# Pow_Dist_24_12_5v.net
KiCad netlist of a schematic drawn in Altium Designer
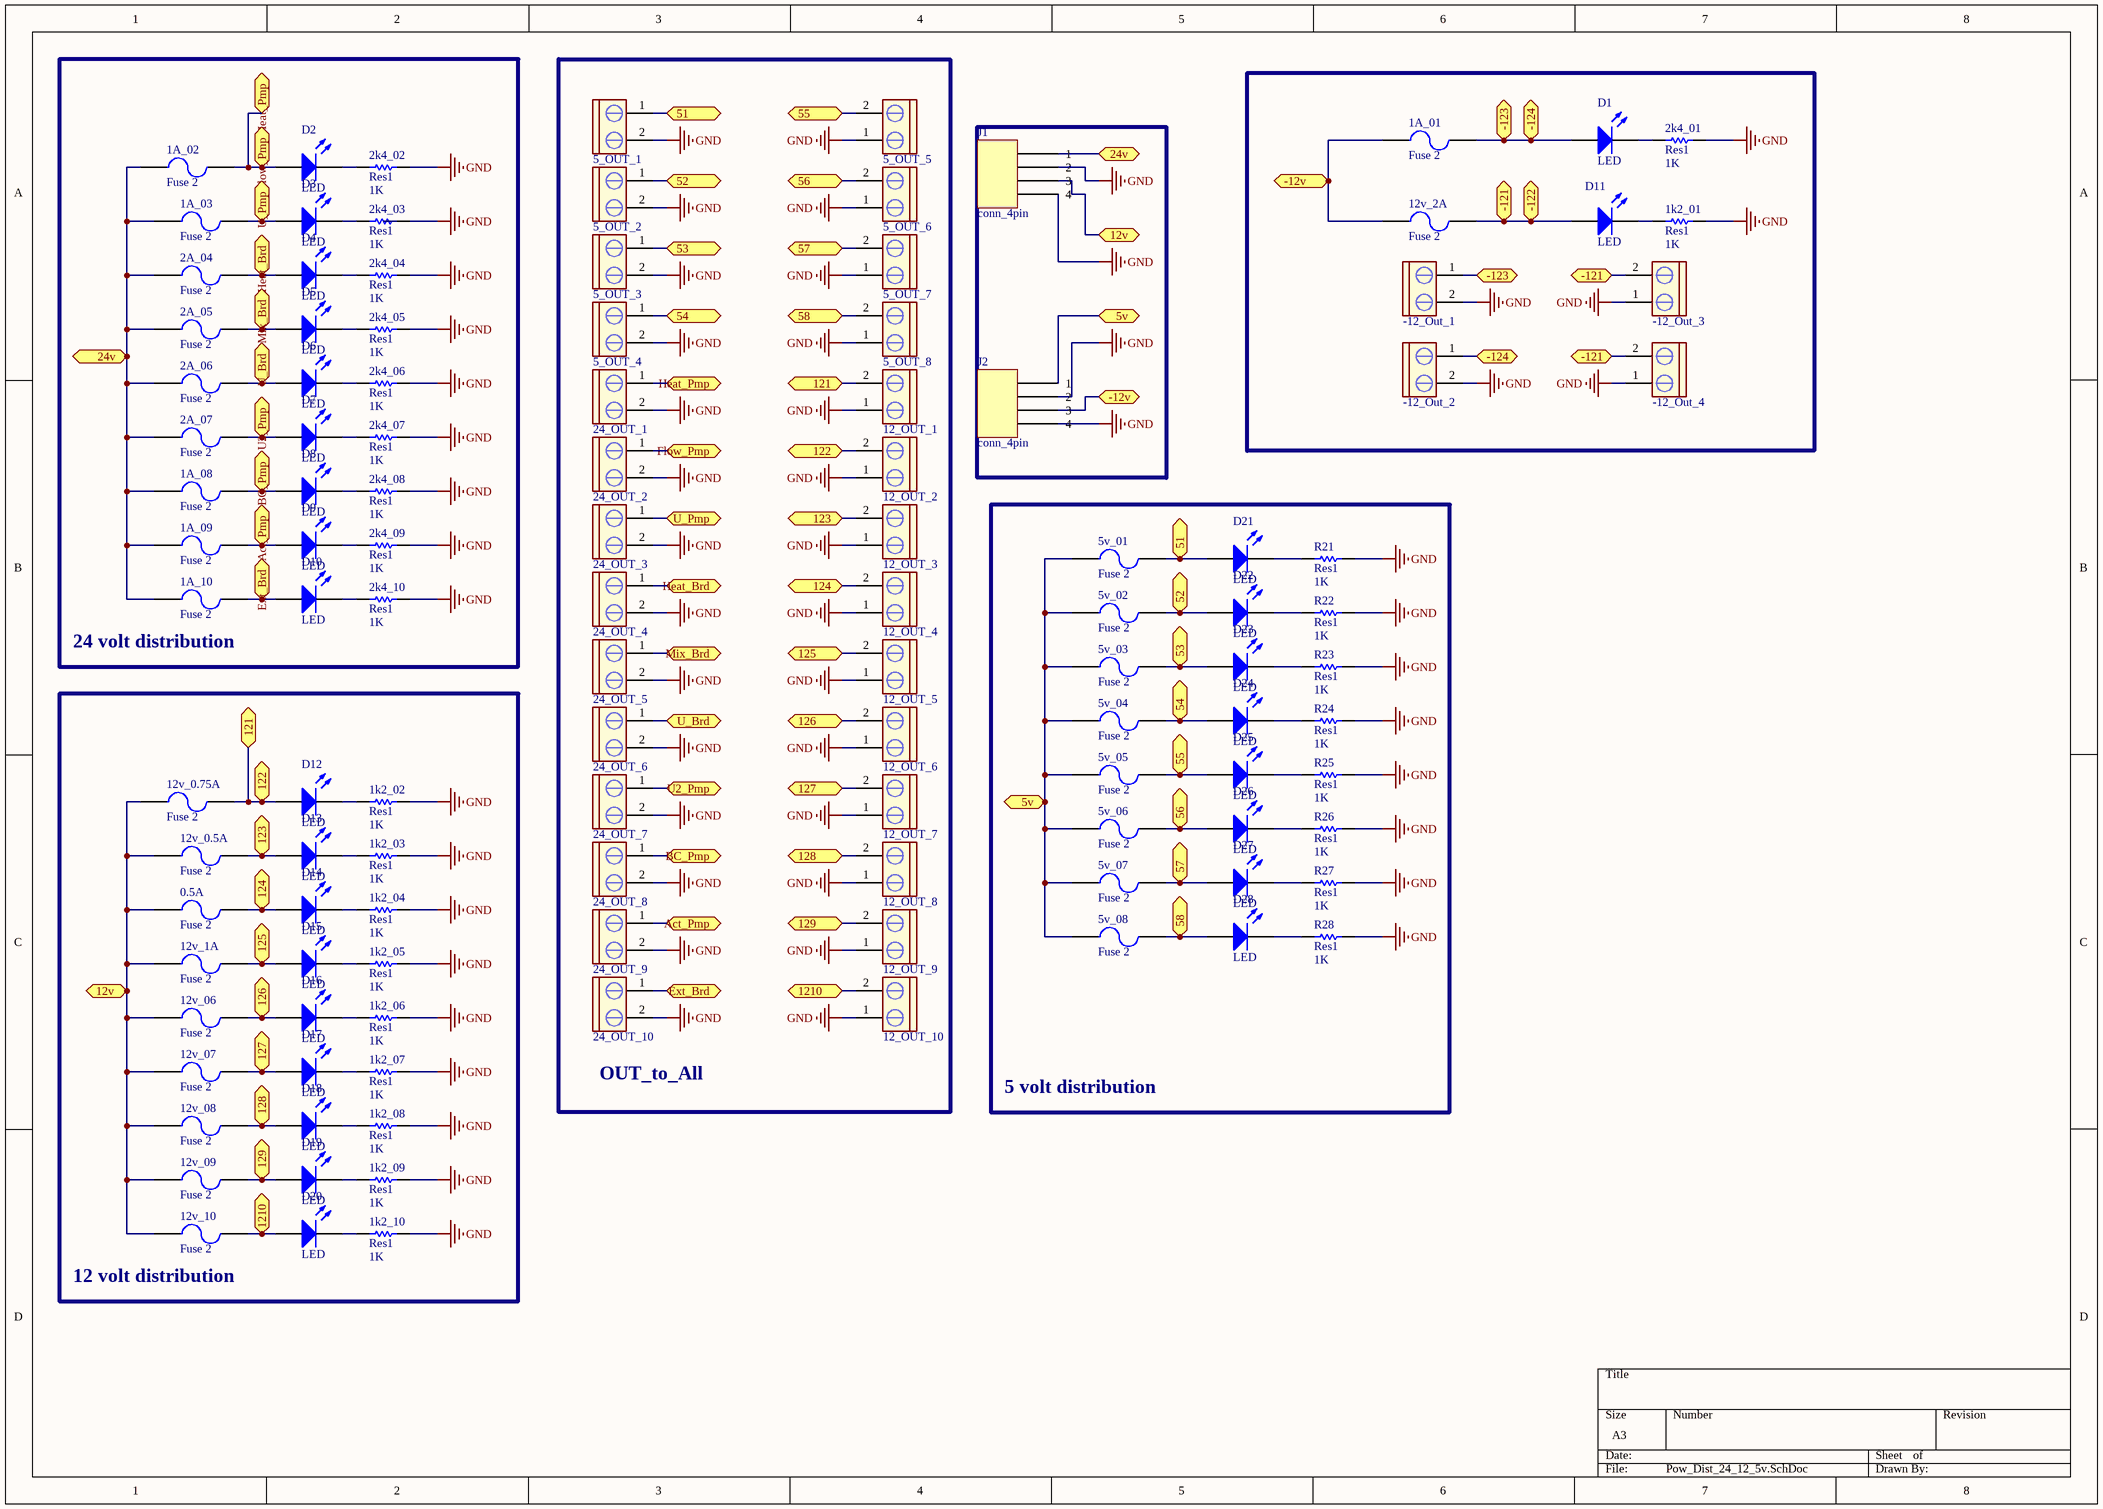
[diagram p0: Pow_Dist_24_12_5v.SchDoc]

(export (version "E")
  (design (tool "Eeschema 10.0.6"))
  (components
    (comp (ref "-12_Out_1")
      (value "CON2 pin blue")
      (footprint "My_CN2")
      (description "Connector blue screw")
      (libsource (lib "Mylib") (part "CON2 pin blue"))
    )
    (comp (ref "-12_Out_2")
      (value "CON2 pin blue")
      (footprint "My_CN2")
      (description "Connector blue screw")
      (libsource (lib "Mylib") (part "CON2 pin blue"))
    )
    (comp (ref "-12_Out_3")
      (value "CON2 pin blue")
      (footprint "My_CN2")
      (description "Connector blue screw")
      (libsource (lib "") (part "CON2 pin blue_1"))
    )
    (comp (ref "-12_Out_4")
      (value "CON2 pin blue")
      (footprint "My_CN2")
      (description "Connector blue screw")
      (libsource (lib "") (part "CON2 pin blue_1"))
    )
    (comp (ref "0.5A")
      (value "Fuse 2")
      (footprint "FUSE:PCBComponent_1")
      (description "Fuse")
      (fields (field (name "PUBLISHER") "Altium Limited"))
      (libsource (lib "Miscellaneous Devices") (part "Fuse 2"))
    )
    (comp (ref "1A_01")
      (value "Fuse 2")
      (footprint "FUSE:PCBComponent_1")
      (description "Fuse")
      (fields (field (name "PUBLISHER") "Altium Limited"))
      (libsource (lib "Miscellaneous Devices") (part "Fuse 2"))
    )
    (comp (ref "1A_02")
      (value "Fuse 2")
      (footprint "FUSE:PCBComponent_1")
      (description "Fuse")
      (fields (field (name "PUBLISHER") "Altium Limited"))
      (libsource (lib "Miscellaneous Devices") (part "Fuse 2"))
    )
    (comp (ref "1A_03")
      (value "Fuse 2")
      (footprint "FUSE:PCBComponent_1")
      (description "Fuse")
      (fields (field (name "PUBLISHER") "Altium Limited"))
      (libsource (lib "Miscellaneous Devices") (part "Fuse 2"))
    )
    (comp (ref "1A_08")
      (value "Fuse 2")
      (footprint "FUSE:PCBComponent_1")
      (description "Fuse")
      (fields (field (name "PUBLISHER") "Altium Limited"))
      (libsource (lib "Miscellaneous Devices") (part "Fuse 2"))
    )
    (comp (ref "1A_09")
      (value "Fuse 2")
      (footprint "FUSE:PCBComponent_1")
      (description "Fuse")
      (fields (field (name "PUBLISHER") "Altium Limited"))
      (libsource (lib "Miscellaneous Devices") (part "Fuse 2"))
    )
    (comp (ref "1A_10")
      (value "Fuse 2")
      (footprint "FUSE:PCBComponent_1")
      (description "Fuse")
      (fields (field (name "PUBLISHER") "Altium Limited"))
      (libsource (lib "Miscellaneous Devices") (part "Fuse 2"))
    )
    (comp (ref "1k2_01")
      (value "Res1")
      (footprint "AXIAL-0.3")
      (description "Resistor")
      (fields (field (name "ALTIUM_VALUE") "1K") (field (name "PUBLISHER") "Altium Limited"))
      (libsource (lib "Miscellaneous Devices") (part "Res1"))
    )
    (comp (ref "1k2_02")
      (value "Res1")
      (footprint "AXIAL-0.3")
      (description "Resistor")
      (fields (field (name "ALTIUM_VALUE") "1K") (field (name "PUBLISHER") "Altium Limited"))
      (libsource (lib "Miscellaneous Devices") (part "Res1"))
    )
    (comp (ref "1k2_03")
      (value "Res1")
      (footprint "AXIAL-0.3")
      (description "Resistor")
      (fields (field (name "ALTIUM_VALUE") "1K") (field (name "PUBLISHER") "Altium Limited"))
      (libsource (lib "Miscellaneous Devices") (part "Res1"))
    )
    (comp (ref "1k2_04")
      (value "Res1")
      (footprint "AXIAL-0.3")
      (description "Resistor")
      (fields (field (name "ALTIUM_VALUE") "1K") (field (name "PUBLISHER") "Altium Limited"))
      (libsource (lib "Miscellaneous Devices") (part "Res1"))
    )
    (comp (ref "1k2_05")
      (value "Res1")
      (footprint "AXIAL-0.3")
      (description "Resistor")
      (fields (field (name "ALTIUM_VALUE") "1K") (field (name "PUBLISHER") "Altium Limited"))
      (libsource (lib "Miscellaneous Devices") (part "Res1"))
    )
    (comp (ref "1k2_06")
      (value "Res1")
      (footprint "AXIAL-0.3")
      (description "Resistor")
      (fields (field (name "ALTIUM_VALUE") "1K") (field (name "PUBLISHER") "Altium Limited"))
      (libsource (lib "Miscellaneous Devices") (part "Res1"))
    )
    (comp (ref "1k2_07")
      (value "Res1")
      (footprint "AXIAL-0.3")
      (description "Resistor")
      (fields (field (name "ALTIUM_VALUE") "1K") (field (name "PUBLISHER") "Altium Limited"))
      (libsource (lib "Miscellaneous Devices") (part "Res1"))
    )
    (comp (ref "1k2_08")
      (value "Res1")
      (footprint "AXIAL-0.3")
      (description "Resistor")
      (fields (field (name "ALTIUM_VALUE") "1K") (field (name "PUBLISHER") "Altium Limited"))
      (libsource (lib "Miscellaneous Devices") (part "Res1"))
    )
    (comp (ref "1k2_09")
      (value "Res1")
      (footprint "AXIAL-0.3")
      (description "Resistor")
      (fields (field (name "ALTIUM_VALUE") "1K") (field (name "PUBLISHER") "Altium Limited"))
      (libsource (lib "Miscellaneous Devices") (part "Res1"))
    )
    (comp (ref "1k2_10")
      (value "Res1")
      (footprint "AXIAL-0.3")
      (description "Resistor")
      (fields (field (name "ALTIUM_VALUE") "1K") (field (name "PUBLISHER") "Altium Limited"))
      (libsource (lib "Miscellaneous Devices") (part "Res1"))
    )
    (comp (ref "2A_04")
      (value "Fuse 2")
      (footprint "FUSE:PCBComponent_1")
      (description "Fuse")
      (fields (field (name "PUBLISHER") "Altium Limited"))
      (libsource (lib "Miscellaneous Devices") (part "Fuse 2"))
    )
    (comp (ref "2A_05")
      (value "Fuse 2")
      (footprint "FUSE:PCBComponent_1")
      (description "Fuse")
      (fields (field (name "PUBLISHER") "Altium Limited"))
      (libsource (lib "Miscellaneous Devices") (part "Fuse 2"))
    )
    (comp (ref "2A_06")
      (value "Fuse 2")
      (footprint "FUSE:PCBComponent_1")
      (description "Fuse")
      (fields (field (name "PUBLISHER") "Altium Limited"))
      (libsource (lib "Miscellaneous Devices") (part "Fuse 2"))
    )
    (comp (ref "2A_07")
      (value "Fuse 2")
      (footprint "FUSE:PCBComponent_1")
      (description "Fuse")
      (fields (field (name "PUBLISHER") "Altium Limited"))
      (libsource (lib "Miscellaneous Devices") (part "Fuse 2"))
    )
    (comp (ref "2k4_01")
      (value "Res1")
      (footprint "AXIAL-0.3")
      (description "Resistor")
      (fields (field (name "ALTIUM_VALUE") "1K") (field (name "PUBLISHER") "Altium Limited"))
      (libsource (lib "Miscellaneous Devices") (part "Res1"))
    )
    (comp (ref "2k4_02")
      (value "Res1")
      (footprint "AXIAL-0.3")
      (description "Resistor")
      (fields (field (name "ALTIUM_VALUE") "1K") (field (name "PUBLISHER") "Altium Limited"))
      (libsource (lib "Miscellaneous Devices") (part "Res1"))
    )
    (comp (ref "2k4_03")
      (value "Res1")
      (footprint "AXIAL-0.3")
      (description "Resistor")
      (fields (field (name "ALTIUM_VALUE") "1K") (field (name "PUBLISHER") "Altium Limited"))
      (libsource (lib "Miscellaneous Devices") (part "Res1"))
    )
    (comp (ref "2k4_04")
      (value "Res1")
      (footprint "AXIAL-0.3")
      (description "Resistor")
      (fields (field (name "ALTIUM_VALUE") "1K") (field (name "PUBLISHER") "Altium Limited"))
      (libsource (lib "Miscellaneous Devices") (part "Res1"))
    )
    (comp (ref "2k4_05")
      (value "Res1")
      (footprint "AXIAL-0.3")
      (description "Resistor")
      (fields (field (name "ALTIUM_VALUE") "1K") (field (name "PUBLISHER") "Altium Limited"))
      (libsource (lib "Miscellaneous Devices") (part "Res1"))
    )
    (comp (ref "2k4_06")
      (value "Res1")
      (footprint "AXIAL-0.3")
      (description "Resistor")
      (fields (field (name "ALTIUM_VALUE") "1K") (field (name "PUBLISHER") "Altium Limited"))
      (libsource (lib "Miscellaneous Devices") (part "Res1"))
    )
    (comp (ref "2k4_07")
      (value "Res1")
      (footprint "AXIAL-0.3")
      (description "Resistor")
      (fields (field (name "ALTIUM_VALUE") "1K") (field (name "PUBLISHER") "Altium Limited"))
      (libsource (lib "Miscellaneous Devices") (part "Res1"))
    )
    (comp (ref "2k4_08")
      (value "Res1")
      (footprint "AXIAL-0.3")
      (description "Resistor")
      (fields (field (name "ALTIUM_VALUE") "1K") (field (name "PUBLISHER") "Altium Limited"))
      (libsource (lib "Miscellaneous Devices") (part "Res1"))
    )
    (comp (ref "2k4_09")
      (value "Res1")
      (footprint "AXIAL-0.3")
      (description "Resistor")
      (fields (field (name "ALTIUM_VALUE") "1K") (field (name "PUBLISHER") "Altium Limited"))
      (libsource (lib "Miscellaneous Devices") (part "Res1"))
    )
    (comp (ref "2k4_10")
      (value "Res1")
      (footprint "AXIAL-0.3")
      (description "Resistor")
      (fields (field (name "ALTIUM_VALUE") "1K") (field (name "PUBLISHER") "Altium Limited"))
      (libsource (lib "Miscellaneous Devices") (part "Res1"))
    )
    (comp (ref "5v_01")
      (value "Fuse 2")
      (footprint "FUSE:PCBComponent_1")
      (description "Fuse")
      (fields (field (name "PUBLISHER") "Altium Limited"))
      (libsource (lib "Miscellaneous Devices") (part "Fuse 2"))
    )
    (comp (ref "5v_02")
      (value "Fuse 2")
      (footprint "FUSE:PCBComponent_1")
      (description "Fuse")
      (fields (field (name "PUBLISHER") "Altium Limited"))
      (libsource (lib "Miscellaneous Devices") (part "Fuse 2"))
    )
    (comp (ref "5v_03")
      (value "Fuse 2")
      (footprint "FUSE:PCBComponent_1")
      (description "Fuse")
      (fields (field (name "PUBLISHER") "Altium Limited"))
      (libsource (lib "Miscellaneous Devices") (part "Fuse 2"))
    )
    (comp (ref "5v_04")
      (value "Fuse 2")
      (footprint "FUSE:PCBComponent_1")
      (description "Fuse")
      (fields (field (name "PUBLISHER") "Altium Limited"))
      (libsource (lib "Miscellaneous Devices") (part "Fuse 2"))
    )
    (comp (ref "5v_05")
      (value "Fuse 2")
      (footprint "FUSE:PCBComponent_1")
      (description "Fuse")
      (fields (field (name "PUBLISHER") "Altium Limited"))
      (libsource (lib "Miscellaneous Devices") (part "Fuse 2"))
    )
    (comp (ref "5v_06")
      (value "Fuse 2")
      (footprint "FUSE:PCBComponent_1")
      (description "Fuse")
      (fields (field (name "PUBLISHER") "Altium Limited"))
      (libsource (lib "Miscellaneous Devices") (part "Fuse 2"))
    )
    (comp (ref "5v_07")
      (value "Fuse 2")
      (footprint "FUSE:PCBComponent_1")
      (description "Fuse")
      (fields (field (name "PUBLISHER") "Altium Limited"))
      (libsource (lib "Miscellaneous Devices") (part "Fuse 2"))
    )
    (comp (ref "5v_08")
      (value "Fuse 2")
      (footprint "FUSE:PCBComponent_1")
      (description "Fuse")
      (fields (field (name "PUBLISHER") "Altium Limited"))
      (libsource (lib "Miscellaneous Devices") (part "Fuse 2"))
    )
    (comp (ref "5_OUT_1")
      (value "CON2 pin blue")
      (footprint "My_CN2")
      (description "Connector blue screw")
      (libsource (lib "Mylib") (part "CON2 pin blue"))
    )
    (comp (ref "5_OUT_2")
      (value "CON2 pin blue")
      (footprint "My_CN2")
      (description "Connector blue screw")
      (libsource (lib "Mylib") (part "CON2 pin blue"))
    )
    (comp (ref "5_OUT_3")
      (value "CON2 pin blue")
      (footprint "My_CN2")
      (description "Connector blue screw")
      (libsource (lib "Mylib") (part "CON2 pin blue"))
    )
    (comp (ref "5_OUT_4")
      (value "CON2 pin blue")
      (footprint "My_CN2")
      (description "Connector blue screw")
      (libsource (lib "Mylib") (part "CON2 pin blue"))
    )
    (comp (ref "5_OUT_5")
      (value "CON2 pin blue")
      (footprint "My_CN2")
      (description "Connector blue screw")
      (libsource (lib "") (part "CON2 pin blue_1"))
    )
    (comp (ref "5_OUT_6")
      (value "CON2 pin blue")
      (footprint "My_CN2")
      (description "Connector blue screw")
      (libsource (lib "") (part "CON2 pin blue_1"))
    )
    (comp (ref "5_OUT_7")
      (value "CON2 pin blue")
      (footprint "My_CN2")
      (description "Connector blue screw")
      (libsource (lib "") (part "CON2 pin blue_1"))
    )
    (comp (ref "5_OUT_8")
      (value "CON2 pin blue")
      (footprint "My_CN2")
      (description "Connector blue screw")
      (libsource (lib "") (part "CON2 pin blue_1"))
    )
    (comp (ref "12v_0.5A")
      (value "Fuse 2")
      (footprint "FUSE:PCBComponent_1")
      (description "Fuse")
      (fields (field (name "PUBLISHER") "Altium Limited"))
      (libsource (lib "Miscellaneous Devices") (part "Fuse 2"))
    )
    (comp (ref "12v_0.75A")
      (value "Fuse 2")
      (footprint "FUSE:PCBComponent_1")
      (description "Fuse")
      (fields (field (name "PUBLISHER") "Altium Limited"))
      (libsource (lib "Miscellaneous Devices") (part "Fuse 2"))
    )
    (comp (ref "12v_1A")
      (value "Fuse 2")
      (footprint "FUSE:PCBComponent_1")
      (description "Fuse")
      (fields (field (name "PUBLISHER") "Altium Limited"))
      (libsource (lib "Miscellaneous Devices") (part "Fuse 2"))
    )
    (comp (ref "12v_2A")
      (value "Fuse 2")
      (footprint "FUSE:PCBComponent_1")
      (description "Fuse")
      (fields (field (name "PUBLISHER") "Altium Limited"))
      (libsource (lib "Miscellaneous Devices") (part "Fuse 2"))
    )
    (comp (ref "12v_06")
      (value "Fuse 2")
      (footprint "FUSE:PCBComponent_1")
      (description "Fuse")
      (fields (field (name "PUBLISHER") "Altium Limited"))
      (libsource (lib "Miscellaneous Devices") (part "Fuse 2"))
    )
    (comp (ref "12v_07")
      (value "Fuse 2")
      (footprint "FUSE:PCBComponent_1")
      (description "Fuse")
      (fields (field (name "PUBLISHER") "Altium Limited"))
      (libsource (lib "Miscellaneous Devices") (part "Fuse 2"))
    )
    (comp (ref "12v_08")
      (value "Fuse 2")
      (footprint "FUSE:PCBComponent_1")
      (description "Fuse")
      (fields (field (name "PUBLISHER") "Altium Limited"))
      (libsource (lib "Miscellaneous Devices") (part "Fuse 2"))
    )
    (comp (ref "12v_09")
      (value "Fuse 2")
      (footprint "FUSE:PCBComponent_1")
      (description "Fuse")
      (fields (field (name "PUBLISHER") "Altium Limited"))
      (libsource (lib "Miscellaneous Devices") (part "Fuse 2"))
    )
    (comp (ref "12v_10")
      (value "Fuse 2")
      (footprint "FUSE:PCBComponent_1")
      (description "Fuse")
      (fields (field (name "PUBLISHER") "Altium Limited"))
      (libsource (lib "Miscellaneous Devices") (part "Fuse 2"))
    )
    (comp (ref "12_OUT_1")
      (value "CON2 pin blue")
      (footprint "My_CN2")
      (description "Connector blue screw")
      (libsource (lib "") (part "CON2 pin blue_1"))
    )
    (comp (ref "12_OUT_2")
      (value "CON2 pin blue")
      (footprint "My_CN2")
      (description "Connector blue screw")
      (libsource (lib "") (part "CON2 pin blue_1"))
    )
    (comp (ref "12_OUT_3")
      (value "CON2 pin blue")
      (footprint "My_CN2")
      (description "Connector blue screw")
      (libsource (lib "") (part "CON2 pin blue_1"))
    )
    (comp (ref "12_OUT_4")
      (value "CON2 pin blue")
      (footprint "My_CN2")
      (description "Connector blue screw")
      (libsource (lib "") (part "CON2 pin blue_1"))
    )
    (comp (ref "12_OUT_5")
      (value "CON2 pin blue")
      (footprint "My_CN2")
      (description "Connector blue screw")
      (libsource (lib "") (part "CON2 pin blue_1"))
    )
    (comp (ref "12_OUT_6")
      (value "CON2 pin blue")
      (footprint "My_CN2")
      (description "Connector blue screw")
      (libsource (lib "") (part "CON2 pin blue_1"))
    )
    (comp (ref "12_OUT_7")
      (value "CON2 pin blue")
      (footprint "My_CN2")
      (description "Connector blue screw")
      (libsource (lib "") (part "CON2 pin blue_1"))
    )
    (comp (ref "12_OUT_8")
      (value "CON2 pin blue")
      (footprint "My_CN2")
      (description "Connector blue screw")
      (libsource (lib "") (part "CON2 pin blue_1"))
    )
    (comp (ref "12_OUT_9")
      (value "CON2 pin blue")
      (footprint "My_CN2")
      (description "Connector blue screw")
      (libsource (lib "") (part "CON2 pin blue_1"))
    )
    (comp (ref "12_OUT_10")
      (value "CON2 pin blue")
      (footprint "My_CN2")
      (description "Connector blue screw")
      (libsource (lib "") (part "CON2 pin blue_1"))
    )
    (comp (ref "24_OUT_1")
      (value "CON2 pin blue")
      (footprint "My_CN2")
      (description "Connector blue screw")
      (libsource (lib "Mylib") (part "CON2 pin blue"))
    )
    (comp (ref "24_OUT_2")
      (value "CON2 pin blue")
      (footprint "My_CN2")
      (description "Connector blue screw")
      (libsource (lib "Mylib") (part "CON2 pin blue"))
    )
    (comp (ref "24_OUT_3")
      (value "CON2 pin blue")
      (footprint "My_CN2")
      (description "Connector blue screw")
      (libsource (lib "Mylib") (part "CON2 pin blue"))
    )
    (comp (ref "24_OUT_4")
      (value "CON2 pin blue")
      (footprint "My_CN2")
      (description "Connector blue screw")
      (libsource (lib "Mylib") (part "CON2 pin blue"))
    )
    (comp (ref "24_OUT_5")
      (value "CON2 pin blue")
      (footprint "My_CN2")
      (description "Connector blue screw")
      (libsource (lib "Mylib") (part "CON2 pin blue"))
    )
    (comp (ref "24_OUT_6")
      (value "CON2 pin blue")
      (footprint "My_CN2")
      (description "Connector blue screw")
      (libsource (lib "Mylib") (part "CON2 pin blue"))
    )
    (comp (ref "24_OUT_7")
      (value "CON2 pin blue")
      (footprint "My_CN2")
      (description "Connector blue screw")
      (libsource (lib "Mylib") (part "CON2 pin blue"))
    )
    (comp (ref "24_OUT_8")
      (value "CON2 pin blue")
      (footprint "My_CN2")
      (description "Connector blue screw")
      (libsource (lib "Mylib") (part "CON2 pin blue"))
    )
    (comp (ref "24_OUT_9")
      (value "CON2 pin blue")
      (footprint "My_CN2")
      (description "Connector blue screw")
      (libsource (lib "Mylib") (part "CON2 pin blue"))
    )
    (comp (ref "24_OUT_10")
      (value "CON2 pin blue")
      (footprint "My_CN2")
      (description "Connector blue screw")
      (libsource (lib "Mylib") (part "CON2 pin blue"))
    )
    (comp (ref "D1")
      (value "LED")
      (footprint "My_LED3MM")
      (description "Typical INFRARED GaAs LED")
      (fields (field (name "PUBLISHER") "Altium Limited"))
      (libsource (lib "Mylib") (part "LED"))
    )
    (comp (ref "D2")
      (value "LED")
      (footprint "My_LED3MM")
      (description "Typical INFRARED GaAs LED")
      (fields (field (name "PUBLISHER") "Altium Limited"))
      (libsource (lib "Mylib") (part "LED"))
    )
    (comp (ref "D3")
      (value "LED")
      (footprint "My_LED3MM")
      (description "Typical INFRARED GaAs LED")
      (fields (field (name "PUBLISHER") "Altium Limited"))
      (libsource (lib "Mylib") (part "LED"))
    )
    (comp (ref "D4")
      (value "LED")
      (footprint "My_LED3MM")
      (description "Typical INFRARED GaAs LED")
      (fields (field (name "PUBLISHER") "Altium Limited"))
      (libsource (lib "Mylib") (part "LED"))
    )
    (comp (ref "D5")
      (value "LED")
      (footprint "My_LED3MM")
      (description "Typical INFRARED GaAs LED")
      (fields (field (name "PUBLISHER") "Altium Limited"))
      (libsource (lib "Mylib") (part "LED"))
    )
    (comp (ref "D6")
      (value "LED")
      (footprint "My_LED3MM")
      (description "Typical INFRARED GaAs LED")
      (fields (field (name "PUBLISHER") "Altium Limited"))
      (libsource (lib "Mylib") (part "LED"))
    )
    (comp (ref "D7")
      (value "LED")
      (footprint "My_LED3MM")
      (description "Typical INFRARED GaAs LED")
      (fields (field (name "PUBLISHER") "Altium Limited"))
      (libsource (lib "Mylib") (part "LED"))
    )
    (comp (ref "D8")
      (value "LED")
      (footprint "My_LED3MM")
      (description "Typical INFRARED GaAs LED")
      (fields (field (name "PUBLISHER") "Altium Limited"))
      (libsource (lib "Mylib") (part "LED"))
    )
    (comp (ref "D9")
      (value "LED")
      (footprint "My_LED3MM")
      (description "Typical INFRARED GaAs LED")
      (fields (field (name "PUBLISHER") "Altium Limited"))
      (libsource (lib "Mylib") (part "LED"))
    )
    (comp (ref "D10")
      (value "LED")
      (footprint "My_LED3MM")
      (description "Typical INFRARED GaAs LED")
      (fields (field (name "PUBLISHER") "Altium Limited"))
      (libsource (lib "Mylib") (part "LED"))
    )
    (comp (ref "D11")
      (value "LED")
      (footprint "My_LED3MM")
      (description "Typical INFRARED GaAs LED")
      (fields (field (name "PUBLISHER") "Altium Limited"))
      (libsource (lib "Mylib") (part "LED"))
    )
    (comp (ref "D12")
      (value "LED")
      (footprint "My_LED3MM")
      (description "Typical INFRARED GaAs LED")
      (fields (field (name "PUBLISHER") "Altium Limited"))
      (libsource (lib "Mylib") (part "LED"))
    )
    (comp (ref "D13")
      (value "LED")
      (footprint "My_LED3MM")
      (description "Typical INFRARED GaAs LED")
      (fields (field (name "PUBLISHER") "Altium Limited"))
      (libsource (lib "Mylib") (part "LED"))
    )
    (comp (ref "D14")
      (value "LED")
      (footprint "My_LED3MM")
      (description "Typical INFRARED GaAs LED")
      (fields (field (name "PUBLISHER") "Altium Limited"))
      (libsource (lib "Mylib") (part "LED"))
    )
    (comp (ref "D15")
      (value "LED")
      (footprint "My_LED3MM")
      (description "Typical INFRARED GaAs LED")
      (fields (field (name "PUBLISHER") "Altium Limited"))
      (libsource (lib "Mylib") (part "LED"))
    )
    (comp (ref "D16")
      (value "LED")
      (footprint "My_LED3MM")
      (description "Typical INFRARED GaAs LED")
      (fields (field (name "PUBLISHER") "Altium Limited"))
      (libsource (lib "Mylib") (part "LED"))
    )
    (comp (ref "D17")
      (value "LED")
      (footprint "My_LED3MM")
      (description "Typical INFRARED GaAs LED")
      (fields (field (name "PUBLISHER") "Altium Limited"))
      (libsource (lib "Mylib") (part "LED"))
    )
    (comp (ref "D18")
      (value "LED")
      (footprint "My_LED3MM")
      (description "Typical INFRARED GaAs LED")
      (fields (field (name "PUBLISHER") "Altium Limited"))
      (libsource (lib "Mylib") (part "LED"))
    )
    (comp (ref "D19")
      (value "LED")
      (footprint "My_LED3MM")
      (description "Typical INFRARED GaAs LED")
      (fields (field (name "PUBLISHER") "Altium Limited"))
      (libsource (lib "Mylib") (part "LED"))
    )
    (comp (ref "D20")
      (value "LED")
      (footprint "My_LED3MM")
      (description "Typical INFRARED GaAs LED")
      (fields (field (name "PUBLISHER") "Altium Limited"))
      (libsource (lib "Mylib") (part "LED"))
    )
    (comp (ref "D21")
      (value "LED")
      (footprint "My_LED3MM")
      (description "Typical INFRARED GaAs LED")
      (fields (field (name "PUBLISHER") "Altium Limited"))
      (libsource (lib "Mylib") (part "LED"))
    )
    (comp (ref "D22")
      (value "LED")
      (footprint "My_LED3MM")
      (description "Typical INFRARED GaAs LED")
      (fields (field (name "PUBLISHER") "Altium Limited"))
      (libsource (lib "Mylib") (part "LED"))
    )
    (comp (ref "D23")
      (value "LED")
      (footprint "My_LED3MM")
      (description "Typical INFRARED GaAs LED")
      (fields (field (name "PUBLISHER") "Altium Limited"))
      (libsource (lib "Mylib") (part "LED"))
    )
    (comp (ref "D24")
      (value "LED")
      (footprint "My_LED3MM")
      (description "Typical INFRARED GaAs LED")
      (fields (field (name "PUBLISHER") "Altium Limited"))
      (libsource (lib "Mylib") (part "LED"))
    )
    (comp (ref "D25")
      (value "LED")
      (footprint "My_LED3MM")
      (description "Typical INFRARED GaAs LED")
      (fields (field (name "PUBLISHER") "Altium Limited"))
      (libsource (lib "Mylib") (part "LED"))
    )
    (comp (ref "D26")
      (value "LED")
      (footprint "My_LED3MM")
      (description "Typical INFRARED GaAs LED")
      (fields (field (name "PUBLISHER") "Altium Limited"))
      (libsource (lib "Mylib") (part "LED"))
    )
    (comp (ref "D27")
      (value "LED")
      (footprint "My_LED3MM")
      (description "Typical INFRARED GaAs LED")
      (fields (field (name "PUBLISHER") "Altium Limited"))
      (libsource (lib "Mylib") (part "LED"))
    )
    (comp (ref "D28")
      (value "LED")
      (footprint "My_LED3MM")
      (description "Typical INFRARED GaAs LED")
      (fields (field (name "PUBLISHER") "Altium Limited"))
      (libsource (lib "Mylib") (part "LED"))
    )
    (comp (ref "J1")
      (value "conn_4pin")
      (footprint "conn_4pin")
      (libsource (lib "conn_4pin") (part "conn_4pin"))
    )
    (comp (ref "J2")
      (value "conn_4pin")
      (footprint "conn_4pin")
      (libsource (lib "conn_4pin") (part "conn_4pin"))
    )
    (comp (ref "R21")
      (value "Res1")
      (footprint "AXIAL-0.3")
      (description "Resistor")
      (fields (field (name "ALTIUM_VALUE") "1K") (field (name "PUBLISHER") "Altium Limited"))
      (libsource (lib "Miscellaneous Devices") (part "Res1"))
    )
    (comp (ref "R22")
      (value "Res1")
      (footprint "AXIAL-0.3")
      (description "Resistor")
      (fields (field (name "ALTIUM_VALUE") "1K") (field (name "PUBLISHER") "Altium Limited"))
      (libsource (lib "Miscellaneous Devices") (part "Res1"))
    )
    (comp (ref "R23")
      (value "Res1")
      (footprint "AXIAL-0.3")
      (description "Resistor")
      (fields (field (name "ALTIUM_VALUE") "1K") (field (name "PUBLISHER") "Altium Limited"))
      (libsource (lib "Miscellaneous Devices") (part "Res1"))
    )
    (comp (ref "R24")
      (value "Res1")
      (footprint "AXIAL-0.3")
      (description "Resistor")
      (fields (field (name "ALTIUM_VALUE") "1K") (field (name "PUBLISHER") "Altium Limited"))
      (libsource (lib "Miscellaneous Devices") (part "Res1"))
    )
    (comp (ref "R25")
      (value "Res1")
      (footprint "AXIAL-0.3")
      (description "Resistor")
      (fields (field (name "ALTIUM_VALUE") "1K") (field (name "PUBLISHER") "Altium Limited"))
      (libsource (lib "Miscellaneous Devices") (part "Res1"))
    )
    (comp (ref "R26")
      (value "Res1")
      (footprint "AXIAL-0.3")
      (description "Resistor")
      (fields (field (name "ALTIUM_VALUE") "1K") (field (name "PUBLISHER") "Altium Limited"))
      (libsource (lib "Miscellaneous Devices") (part "Res1"))
    )
    (comp (ref "R27")
      (value "Res1")
      (footprint "AXIAL-0.3")
      (description "Resistor")
      (fields (field (name "ALTIUM_VALUE") "1K") (field (name "PUBLISHER") "Altium Limited"))
      (libsource (lib "Miscellaneous Devices") (part "Res1"))
    )
    (comp (ref "R28")
      (value "Res1")
      (footprint "AXIAL-0.3")
      (description "Resistor")
      (fields (field (name "ALTIUM_VALUE") "1K") (field (name "PUBLISHER") "Altium Limited"))
      (libsource (lib "Miscellaneous Devices") (part "Res1"))
    )
  )
  (nets
    (net (code "1") (name "/-12v") (class "Default")
      (node (ref "12v_2A") (pin "1") (pinfunction "1_1") (pintype "passive"))
      (node (ref "1A_01") (pin "1") (pinfunction "1_1") (pintype "passive"))
    )
    (net (code "2") (name "/-121") (class "Default")
      (node (ref "-12_Out_3") (pin "2") (pinfunction "2_2") (pintype "passive"))
      (node (ref "-12_Out_4") (pin "2") (pinfunction "2_2") (pintype "passive"))
      (node (ref "12v_2A") (pin "2") (pinfunction "2_2") (pintype "passive"))
      (node (ref "D11") (pin "A") (pinfunction "A_A") (pintype "passive"))
    )
    (net (code "3") (name "/-123") (class "Default")
      (node (ref "-12_Out_1") (pin "1") (pinfunction "1_1") (pintype "passive"))
      (node (ref "-12_Out_2") (pin "1") (pinfunction "1_1") (pintype "passive"))
      (node (ref "1A_01") (pin "2") (pinfunction "2_2") (pintype "passive"))
      (node (ref "D1") (pin "A") (pinfunction "A_A") (pintype "passive"))
    )
    (net (code "4") (name "/5v") (class "Default")
      (node (ref "5v_01") (pin "1") (pinfunction "1_1") (pintype "passive"))
      (node (ref "5v_02") (pin "1") (pinfunction "1_1") (pintype "passive"))
      (node (ref "5v_03") (pin "1") (pinfunction "1_1") (pintype "passive"))
      (node (ref "5v_04") (pin "1") (pinfunction "1_1") (pintype "passive"))
      (node (ref "5v_05") (pin "1") (pinfunction "1_1") (pintype "passive"))
      (node (ref "5v_06") (pin "1") (pinfunction "1_1") (pintype "passive"))
      (node (ref "5v_07") (pin "1") (pinfunction "1_1") (pintype "passive"))
      (node (ref "5v_08") (pin "1") (pinfunction "1_1") (pintype "passive"))
    )
    (net (code "5") (name "/12v") (class "Default")
      (node (ref "0.5A") (pin "1") (pinfunction "1_1") (pintype "passive"))
      (node (ref "12v_0.5A") (pin "1") (pinfunction "1_1") (pintype "passive"))
      (node (ref "12v_0.75A") (pin "1") (pinfunction "1_1") (pintype "passive"))
      (node (ref "12v_06") (pin "1") (pinfunction "1_1") (pintype "passive"))
      (node (ref "12v_07") (pin "1") (pinfunction "1_1") (pintype "passive"))
      (node (ref "12v_08") (pin "1") (pinfunction "1_1") (pintype "passive"))
      (node (ref "12v_09") (pin "1") (pinfunction "1_1") (pintype "passive"))
      (node (ref "12v_10") (pin "1") (pinfunction "1_1") (pintype "passive"))
      (node (ref "12v_1A") (pin "1") (pinfunction "1_1") (pintype "passive"))
    )
    (net (code "6") (name "/24v") (class "Default")
      (node (ref "1A_02") (pin "1") (pinfunction "1_1") (pintype "passive"))
      (node (ref "1A_03") (pin "1") (pinfunction "1_1") (pintype "passive"))
      (node (ref "1A_08") (pin "1") (pinfunction "1_1") (pintype "passive"))
      (node (ref "1A_09") (pin "1") (pinfunction "1_1") (pintype "passive"))
      (node (ref "1A_10") (pin "1") (pinfunction "1_1") (pintype "passive"))
      (node (ref "2A_04") (pin "1") (pinfunction "1_1") (pintype "passive"))
      (node (ref "2A_05") (pin "1") (pinfunction "1_1") (pintype "passive"))
      (node (ref "2A_06") (pin "1") (pinfunction "1_1") (pintype "passive"))
      (node (ref "2A_07") (pin "1") (pinfunction "1_1") (pintype "passive"))
    )
    (net (code "7") (name "/51") (class "Default")
      (node (ref "5_OUT_1") (pin "1") (pinfunction "1_1") (pintype "passive"))
      (node (ref "5v_01") (pin "2") (pinfunction "2_2") (pintype "passive"))
      (node (ref "D21") (pin "A") (pinfunction "A_A") (pintype "passive"))
    )
    (net (code "8") (name "/52") (class "Default")
      (node (ref "5_OUT_2") (pin "1") (pinfunction "1_1") (pintype "passive"))
      (node (ref "5v_02") (pin "2") (pinfunction "2_2") (pintype "passive"))
      (node (ref "D22") (pin "A") (pinfunction "A_A") (pintype "passive"))
    )
    (net (code "9") (name "/53") (class "Default")
      (node (ref "5_OUT_3") (pin "1") (pinfunction "1_1") (pintype "passive"))
      (node (ref "5v_03") (pin "2") (pinfunction "2_2") (pintype "passive"))
      (node (ref "D23") (pin "A") (pinfunction "A_A") (pintype "passive"))
    )
    (net (code "10") (name "/54") (class "Default")
      (node (ref "5_OUT_4") (pin "1") (pinfunction "1_1") (pintype "passive"))
      (node (ref "5v_04") (pin "2") (pinfunction "2_2") (pintype "passive"))
      (node (ref "D24") (pin "A") (pinfunction "A_A") (pintype "passive"))
    )
    (net (code "11") (name "/55") (class "Default")
      (node (ref "5_OUT_5") (pin "2") (pinfunction "2_2") (pintype "passive"))
      (node (ref "5v_05") (pin "2") (pinfunction "2_2") (pintype "passive"))
      (node (ref "D25") (pin "A") (pinfunction "A_A") (pintype "passive"))
    )
    (net (code "12") (name "/56") (class "Default")
      (node (ref "5_OUT_6") (pin "2") (pinfunction "2_2") (pintype "passive"))
      (node (ref "5v_06") (pin "2") (pinfunction "2_2") (pintype "passive"))
      (node (ref "D26") (pin "A") (pinfunction "A_A") (pintype "passive"))
    )
    (net (code "13") (name "/57") (class "Default")
      (node (ref "5_OUT_7") (pin "2") (pinfunction "2_2") (pintype "passive"))
      (node (ref "5v_07") (pin "2") (pinfunction "2_2") (pintype "passive"))
      (node (ref "D27") (pin "A") (pinfunction "A_A") (pintype "passive"))
    )
    (net (code "14") (name "/58") (class "Default")
      (node (ref "5_OUT_8") (pin "2") (pinfunction "2_2") (pintype "passive"))
      (node (ref "5v_08") (pin "2") (pinfunction "2_2") (pintype "passive"))
      (node (ref "D28") (pin "A") (pinfunction "A_A") (pintype "passive"))
    )
    (net (code "15") (name "/121") (class "Default")
      (node (ref "12_OUT_1") (pin "2") (pinfunction "2_2") (pintype "passive"))
      (node (ref "12_OUT_2") (pin "2") (pinfunction "2_2") (pintype "passive"))
      (node (ref "12v_0.75A") (pin "2") (pinfunction "2_2") (pintype "passive"))
      (node (ref "D12") (pin "A") (pinfunction "A_A") (pintype "passive"))
    )
    (net (code "16") (name "/123") (class "Default")
      (node (ref "12_OUT_3") (pin "2") (pinfunction "2_2") (pintype "passive"))
      (node (ref "12v_0.5A") (pin "2") (pinfunction "2_2") (pintype "passive"))
      (node (ref "D13") (pin "A") (pinfunction "A_A") (pintype "passive"))
    )
    (net (code "17") (name "/124") (class "Default")
      (node (ref "0.5A") (pin "2") (pinfunction "2_2") (pintype "passive"))
      (node (ref "12_OUT_4") (pin "2") (pinfunction "2_2") (pintype "passive"))
      (node (ref "D14") (pin "A") (pinfunction "A_A") (pintype "passive"))
    )
    (net (code "18") (name "/125") (class "Default")
      (node (ref "12_OUT_5") (pin "2") (pinfunction "2_2") (pintype "passive"))
      (node (ref "12v_1A") (pin "2") (pinfunction "2_2") (pintype "passive"))
      (node (ref "D15") (pin "A") (pinfunction "A_A") (pintype "passive"))
    )
    (net (code "19") (name "/126") (class "Default")
      (node (ref "12_OUT_6") (pin "2") (pinfunction "2_2") (pintype "passive"))
      (node (ref "12v_06") (pin "2") (pinfunction "2_2") (pintype "passive"))
      (node (ref "D16") (pin "A") (pinfunction "A_A") (pintype "passive"))
    )
    (net (code "20") (name "/127") (class "Default")
      (node (ref "12_OUT_7") (pin "2") (pinfunction "2_2") (pintype "passive"))
      (node (ref "12v_07") (pin "2") (pinfunction "2_2") (pintype "passive"))
      (node (ref "D17") (pin "A") (pinfunction "A_A") (pintype "passive"))
    )
    (net (code "21") (name "/128") (class "Default")
      (node (ref "12_OUT_8") (pin "2") (pinfunction "2_2") (pintype "passive"))
      (node (ref "12v_08") (pin "2") (pinfunction "2_2") (pintype "passive"))
      (node (ref "D18") (pin "A") (pinfunction "A_A") (pintype "passive"))
    )
    (net (code "22") (name "/129") (class "Default")
      (node (ref "12_OUT_9") (pin "2") (pinfunction "2_2") (pintype "passive"))
      (node (ref "12v_09") (pin "2") (pinfunction "2_2") (pintype "passive"))
      (node (ref "D19") (pin "A") (pinfunction "A_A") (pintype "passive"))
    )
    (net (code "23") (name "/1210") (class "Default")
      (node (ref "12_OUT_10") (pin "2") (pinfunction "2_2") (pintype "passive"))
      (node (ref "12v_10") (pin "2") (pinfunction "2_2") (pintype "passive"))
      (node (ref "D20") (pin "A") (pinfunction "A_A") (pintype "passive"))
    )
    (net (code "24") (name "/Act_Pmp") (class "Default")
      (node (ref "1A_09") (pin "2") (pinfunction "2_2") (pintype "passive"))
      (node (ref "24_OUT_9") (pin "1") (pinfunction "1_1") (pintype "passive"))
      (node (ref "D9") (pin "A") (pinfunction "A_A") (pintype "passive"))
    )
    (net (code "25") (name "/BC_Pmp") (class "Default")
      (node (ref "1A_08") (pin "2") (pinfunction "2_2") (pintype "passive"))
      (node (ref "24_OUT_8") (pin "1") (pinfunction "1_1") (pintype "passive"))
      (node (ref "D8") (pin "A") (pinfunction "A_A") (pintype "passive"))
    )
    (net (code "26") (name "/Ext_Brd") (class "Default")
      (node (ref "1A_10") (pin "2") (pinfunction "2_2") (pintype "passive"))
      (node (ref "24_OUT_10") (pin "1") (pinfunction "1_1") (pintype "passive"))
      (node (ref "D10") (pin "A") (pinfunction "A_A") (pintype "passive"))
    )
    (net (code "27") (name "/Flow_Pmp") (class "Default")
      (node (ref "1A_02") (pin "2") (pinfunction "2_2") (pintype "passive"))
      (node (ref "24_OUT_1") (pin "1") (pinfunction "1_1") (pintype "passive"))
      (node (ref "24_OUT_2") (pin "1") (pinfunction "1_1") (pintype "passive"))
      (node (ref "D2") (pin "A") (pinfunction "A_A") (pintype "passive"))
    )
    (net (code "28") (name "/Heat_Brd") (class "Default")
      (node (ref "24_OUT_4") (pin "1") (pinfunction "1_1") (pintype "passive"))
      (node (ref "2A_04") (pin "2") (pinfunction "2_2") (pintype "passive"))
      (node (ref "D4") (pin "A") (pinfunction "A_A") (pintype "passive"))
    )
    (net (code "29") (name "/Mix_Brd") (class "Default")
      (node (ref "24_OUT_5") (pin "1") (pinfunction "1_1") (pintype "passive"))
      (node (ref "2A_05") (pin "2") (pinfunction "2_2") (pintype "passive"))
      (node (ref "D5") (pin "A") (pinfunction "A_A") (pintype "passive"))
    )
    (net (code "30") (name "/U2_Pmp") (class "Default")
      (node (ref "24_OUT_7") (pin "1") (pinfunction "1_1") (pintype "passive"))
      (node (ref "2A_07") (pin "2") (pinfunction "2_2") (pintype "passive"))
      (node (ref "D7") (pin "A") (pinfunction "A_A") (pintype "passive"))
    )
    (net (code "31") (name "/U_Brd") (class "Default")
      (node (ref "24_OUT_6") (pin "1") (pinfunction "1_1") (pintype "passive"))
      (node (ref "2A_06") (pin "2") (pinfunction "2_2") (pintype "passive"))
      (node (ref "D6") (pin "A") (pinfunction "A_A") (pintype "passive"))
    )
    (net (code "32") (name "/U_Pmp") (class "Default")
      (node (ref "1A_03") (pin "2") (pinfunction "2_2") (pintype "passive"))
      (node (ref "24_OUT_3") (pin "1") (pinfunction "1_1") (pintype "passive"))
      (node (ref "D3") (pin "A") (pinfunction "A_A") (pintype "passive"))
    )
    (net (code "33") (name "GND") (class "Default")
      (node (ref "-12_Out_1") (pin "2") (pinfunction "2_2") (pintype "passive"))
      (node (ref "-12_Out_2") (pin "2") (pinfunction "2_2") (pintype "passive"))
      (node (ref "-12_Out_3") (pin "1") (pinfunction "1_1") (pintype "passive"))
      (node (ref "-12_Out_4") (pin "1") (pinfunction "1_1") (pintype "passive"))
      (node (ref "12_OUT_1") (pin "1") (pinfunction "1_1") (pintype "passive"))
      (node (ref "12_OUT_10") (pin "1") (pinfunction "1_1") (pintype "passive"))
      (node (ref "12_OUT_2") (pin "1") (pinfunction "1_1") (pintype "passive"))
      (node (ref "12_OUT_3") (pin "1") (pinfunction "1_1") (pintype "passive"))
      (node (ref "12_OUT_4") (pin "1") (pinfunction "1_1") (pintype "passive"))
      (node (ref "12_OUT_5") (pin "1") (pinfunction "1_1") (pintype "passive"))
      (node (ref "12_OUT_6") (pin "1") (pinfunction "1_1") (pintype "passive"))
      (node (ref "12_OUT_7") (pin "1") (pinfunction "1_1") (pintype "passive"))
      (node (ref "12_OUT_8") (pin "1") (pinfunction "1_1") (pintype "passive"))
      (node (ref "12_OUT_9") (pin "1") (pinfunction "1_1") (pintype "passive"))
      (node (ref "1k2_01") (pin "2") (pinfunction "2_2") (pintype "passive"))
      (node (ref "1k2_02") (pin "2") (pinfunction "2_2") (pintype "passive"))
      (node (ref "1k2_03") (pin "2") (pinfunction "2_2") (pintype "passive"))
      (node (ref "1k2_04") (pin "2") (pinfunction "2_2") (pintype "passive"))
      (node (ref "1k2_05") (pin "2") (pinfunction "2_2") (pintype "passive"))
      (node (ref "1k2_06") (pin "2") (pinfunction "2_2") (pintype "passive"))
      (node (ref "1k2_07") (pin "2") (pinfunction "2_2") (pintype "passive"))
      (node (ref "1k2_08") (pin "2") (pinfunction "2_2") (pintype "passive"))
      (node (ref "1k2_09") (pin "2") (pinfunction "2_2") (pintype "passive"))
      (node (ref "1k2_10") (pin "2") (pinfunction "2_2") (pintype "passive"))
      (node (ref "24_OUT_1") (pin "2") (pinfunction "2_2") (pintype "passive"))
      (node (ref "24_OUT_10") (pin "2") (pinfunction "2_2") (pintype "passive"))
      (node (ref "24_OUT_2") (pin "2") (pinfunction "2_2") (pintype "passive"))
      (node (ref "24_OUT_3") (pin "2") (pinfunction "2_2") (pintype "passive"))
      (node (ref "24_OUT_4") (pin "2") (pinfunction "2_2") (pintype "passive"))
      (node (ref "24_OUT_5") (pin "2") (pinfunction "2_2") (pintype "passive"))
      (node (ref "24_OUT_6") (pin "2") (pinfunction "2_2") (pintype "passive"))
      (node (ref "24_OUT_7") (pin "2") (pinfunction "2_2") (pintype "passive"))
      (node (ref "24_OUT_8") (pin "2") (pinfunction "2_2") (pintype "passive"))
      (node (ref "24_OUT_9") (pin "2") (pinfunction "2_2") (pintype "passive"))
      (node (ref "2k4_01") (pin "2") (pinfunction "2_2") (pintype "passive"))
      (node (ref "2k4_02") (pin "2") (pinfunction "2_2") (pintype "passive"))
      (node (ref "2k4_03") (pin "2") (pinfunction "2_2") (pintype "passive"))
      (node (ref "2k4_04") (pin "2") (pinfunction "2_2") (pintype "passive"))
      (node (ref "2k4_05") (pin "2") (pinfunction "2_2") (pintype "passive"))
      (node (ref "2k4_06") (pin "2") (pinfunction "2_2") (pintype "passive"))
      (node (ref "2k4_07") (pin "2") (pinfunction "2_2") (pintype "passive"))
      (node (ref "2k4_08") (pin "2") (pinfunction "2_2") (pintype "passive"))
      (node (ref "2k4_09") (pin "2") (pinfunction "2_2") (pintype "passive"))
      (node (ref "2k4_10") (pin "2") (pinfunction "2_2") (pintype "passive"))
      (node (ref "5_OUT_1") (pin "2") (pinfunction "2_2") (pintype "passive"))
      (node (ref "5_OUT_2") (pin "2") (pinfunction "2_2") (pintype "passive"))
      (node (ref "5_OUT_3") (pin "2") (pinfunction "2_2") (pintype "passive"))
      (node (ref "5_OUT_4") (pin "2") (pinfunction "2_2") (pintype "passive"))
      (node (ref "5_OUT_5") (pin "1") (pinfunction "1_1") (pintype "passive"))
      (node (ref "5_OUT_6") (pin "1") (pinfunction "1_1") (pintype "passive"))
      (node (ref "5_OUT_7") (pin "1") (pinfunction "1_1") (pintype "passive"))
      (node (ref "5_OUT_8") (pin "1") (pinfunction "1_1") (pintype "passive"))
      (node (ref "R21") (pin "2") (pinfunction "2_2") (pintype "passive"))
      (node (ref "R22") (pin "2") (pinfunction "2_2") (pintype "passive"))
      (node (ref "R23") (pin "2") (pinfunction "2_2") (pintype "passive"))
      (node (ref "R24") (pin "2") (pinfunction "2_2") (pintype "passive"))
      (node (ref "R25") (pin "2") (pinfunction "2_2") (pintype "passive"))
      (node (ref "R26") (pin "2") (pinfunction "2_2") (pintype "passive"))
      (node (ref "R27") (pin "2") (pinfunction "2_2") (pintype "passive"))
      (node (ref "R28") (pin "2") (pinfunction "2_2") (pintype "passive"))
    )
    (net (code "34") (name "Net-(1k2_01-Pad1)") (class "Default")
      (node (ref "1k2_01") (pin "1") (pinfunction "1_1") (pintype "passive"))
      (node (ref "D11") (pin "K") (pinfunction "K_K") (pintype "passive"))
    )
    (net (code "35") (name "Net-(1k2_02-Pad1)") (class "Default")
      (node (ref "1k2_02") (pin "1") (pinfunction "1_1") (pintype "passive"))
      (node (ref "D12") (pin "K") (pinfunction "K_K") (pintype "passive"))
    )
    (net (code "36") (name "Net-(1k2_03-Pad1)") (class "Default")
      (node (ref "1k2_03") (pin "1") (pinfunction "1_1") (pintype "passive"))
      (node (ref "D13") (pin "K") (pinfunction "K_K") (pintype "passive"))
    )
    (net (code "37") (name "Net-(1k2_04-Pad1)") (class "Default")
      (node (ref "1k2_04") (pin "1") (pinfunction "1_1") (pintype "passive"))
      (node (ref "D14") (pin "K") (pinfunction "K_K") (pintype "passive"))
    )
    (net (code "38") (name "Net-(1k2_05-Pad1)") (class "Default")
      (node (ref "1k2_05") (pin "1") (pinfunction "1_1") (pintype "passive"))
      (node (ref "D15") (pin "K") (pinfunction "K_K") (pintype "passive"))
    )
    (net (code "39") (name "Net-(1k2_06-Pad1)") (class "Default")
      (node (ref "1k2_06") (pin "1") (pinfunction "1_1") (pintype "passive"))
      (node (ref "D16") (pin "K") (pinfunction "K_K") (pintype "passive"))
    )
    (net (code "40") (name "Net-(1k2_07-Pad1)") (class "Default")
      (node (ref "1k2_07") (pin "1") (pinfunction "1_1") (pintype "passive"))
      (node (ref "D17") (pin "K") (pinfunction "K_K") (pintype "passive"))
    )
    (net (code "41") (name "Net-(1k2_08-Pad1)") (class "Default")
      (node (ref "1k2_08") (pin "1") (pinfunction "1_1") (pintype "passive"))
      (node (ref "D18") (pin "K") (pinfunction "K_K") (pintype "passive"))
    )
    (net (code "42") (name "Net-(1k2_09-Pad1)") (class "Default")
      (node (ref "1k2_09") (pin "1") (pinfunction "1_1") (pintype "passive"))
      (node (ref "D19") (pin "K") (pinfunction "K_K") (pintype "passive"))
    )
    (net (code "43") (name "Net-(1k2_10-Pad1)") (class "Default")
      (node (ref "1k2_10") (pin "1") (pinfunction "1_1") (pintype "passive"))
      (node (ref "D20") (pin "K") (pinfunction "K_K") (pintype "passive"))
    )
    (net (code "44") (name "Net-(2k4_01-Pad1)") (class "Default")
      (node (ref "2k4_01") (pin "1") (pinfunction "1_1") (pintype "passive"))
      (node (ref "D1") (pin "K") (pinfunction "K_K") (pintype "passive"))
    )
    (net (code "45") (name "Net-(2k4_02-Pad1)") (class "Default")
      (node (ref "2k4_02") (pin "1") (pinfunction "1_1") (pintype "passive"))
      (node (ref "D2") (pin "K") (pinfunction "K_K") (pintype "passive"))
    )
    (net (code "46") (name "Net-(2k4_03-Pad1)") (class "Default")
      (node (ref "2k4_03") (pin "1") (pinfunction "1_1") (pintype "passive"))
      (node (ref "D3") (pin "K") (pinfunction "K_K") (pintype "passive"))
    )
    (net (code "47") (name "Net-(2k4_04-Pad1)") (class "Default")
      (node (ref "2k4_04") (pin "1") (pinfunction "1_1") (pintype "passive"))
      (node (ref "D4") (pin "K") (pinfunction "K_K") (pintype "passive"))
    )
    (net (code "48") (name "Net-(2k4_05-Pad1)") (class "Default")
      (node (ref "2k4_05") (pin "1") (pinfunction "1_1") (pintype "passive"))
      (node (ref "D5") (pin "K") (pinfunction "K_K") (pintype "passive"))
    )
    (net (code "49") (name "Net-(2k4_06-Pad1)") (class "Default")
      (node (ref "2k4_06") (pin "1") (pinfunction "1_1") (pintype "passive"))
      (node (ref "D6") (pin "K") (pinfunction "K_K") (pintype "passive"))
    )
    (net (code "50") (name "Net-(2k4_07-Pad1)") (class "Default")
      (node (ref "2k4_07") (pin "1") (pinfunction "1_1") (pintype "passive"))
      (node (ref "D7") (pin "K") (pinfunction "K_K") (pintype "passive"))
    )
    (net (code "51") (name "Net-(2k4_08-Pad1)") (class "Default")
      (node (ref "2k4_08") (pin "1") (pinfunction "1_1") (pintype "passive"))
      (node (ref "D8") (pin "K") (pinfunction "K_K") (pintype "passive"))
    )
    (net (code "52") (name "Net-(2k4_09-Pad1)") (class "Default")
      (node (ref "2k4_09") (pin "1") (pinfunction "1_1") (pintype "passive"))
      (node (ref "D9") (pin "K") (pinfunction "K_K") (pintype "passive"))
    )
    (net (code "53") (name "Net-(2k4_10-Pad1)") (class "Default")
      (node (ref "2k4_10") (pin "1") (pinfunction "1_1") (pintype "passive"))
      (node (ref "D10") (pin "K") (pinfunction "K_K") (pintype "passive"))
    )
    (net (code "54") (name "Net-(D21-PadK)") (class "Default")
      (node (ref "D21") (pin "K") (pinfunction "K_K") (pintype "passive"))
      (node (ref "R21") (pin "1") (pinfunction "1_1") (pintype "passive"))
    )
    (net (code "55") (name "Net-(D22-PadK)") (class "Default")
      (node (ref "D22") (pin "K") (pinfunction "K_K") (pintype "passive"))
      (node (ref "R22") (pin "1") (pinfunction "1_1") (pintype "passive"))
    )
    (net (code "56") (name "Net-(D23-PadK)") (class "Default")
      (node (ref "D23") (pin "K") (pinfunction "K_K") (pintype "passive"))
      (node (ref "R23") (pin "1") (pinfunction "1_1") (pintype "passive"))
    )
    (net (code "57") (name "Net-(D24-PadK)") (class "Default")
      (node (ref "D24") (pin "K") (pinfunction "K_K") (pintype "passive"))
      (node (ref "R24") (pin "1") (pinfunction "1_1") (pintype "passive"))
    )
    (net (code "58") (name "Net-(D25-PadK)") (class "Default")
      (node (ref "D25") (pin "K") (pinfunction "K_K") (pintype "passive"))
      (node (ref "R25") (pin "1") (pinfunction "1_1") (pintype "passive"))
    )
    (net (code "59") (name "Net-(D26-PadK)") (class "Default")
      (node (ref "D26") (pin "K") (pinfunction "K_K") (pintype "passive"))
      (node (ref "R26") (pin "1") (pinfunction "1_1") (pintype "passive"))
    )
    (net (code "60") (name "Net-(D27-PadK)") (class "Default")
      (node (ref "D27") (pin "K") (pinfunction "K_K") (pintype "passive"))
      (node (ref "R27") (pin "1") (pinfunction "1_1") (pintype "passive"))
    )
    (net (code "61") (name "Net-(D28-PadK)") (class "Default")
      (node (ref "D28") (pin "K") (pinfunction "K_K") (pintype "passive"))
      (node (ref "R28") (pin "1") (pinfunction "1_1") (pintype "passive"))
    )
    (net (code "62") (name "unconnected-(J1-Pad1)") (class "Default")
      (node (ref "J1") (pin "1") (pinfunction "1_1") (pintype "passive"))
    )
    (net (code "63") (name "unconnected-(J1-Pad2)") (class "Default")
      (node (ref "J1") (pin "2") (pinfunction "2_2") (pintype "passive"))
    )
    (net (code "64") (name "unconnected-(J1-Pad3)") (class "Default")
      (node (ref "J1") (pin "3") (pinfunction "3_3") (pintype "passive"))
    )
    (net (code "65") (name "unconnected-(J1-Pad4)") (class "Default")
      (node (ref "J1") (pin "4") (pinfunction "4_4") (pintype "passive"))
    )
    (net (code "66") (name "unconnected-(J2-Pad1)") (class "Default")
      (node (ref "J2") (pin "1") (pinfunction "1_1") (pintype "passive"))
    )
    (net (code "67") (name "unconnected-(J2-Pad2)") (class "Default")
      (node (ref "J2") (pin "2") (pinfunction "2_2") (pintype "passive"))
    )
    (net (code "68") (name "unconnected-(J2-Pad3)") (class "Default")
      (node (ref "J2") (pin "3") (pinfunction "3_3") (pintype "passive"))
    )
    (net (code "69") (name "unconnected-(J2-Pad4)") (class "Default")
      (node (ref "J2") (pin "4") (pinfunction "4_4") (pintype "passive"))
    )
  )
)
